# Sheet1.net
KiCad netlist of a schematic drawn in Altium Designer
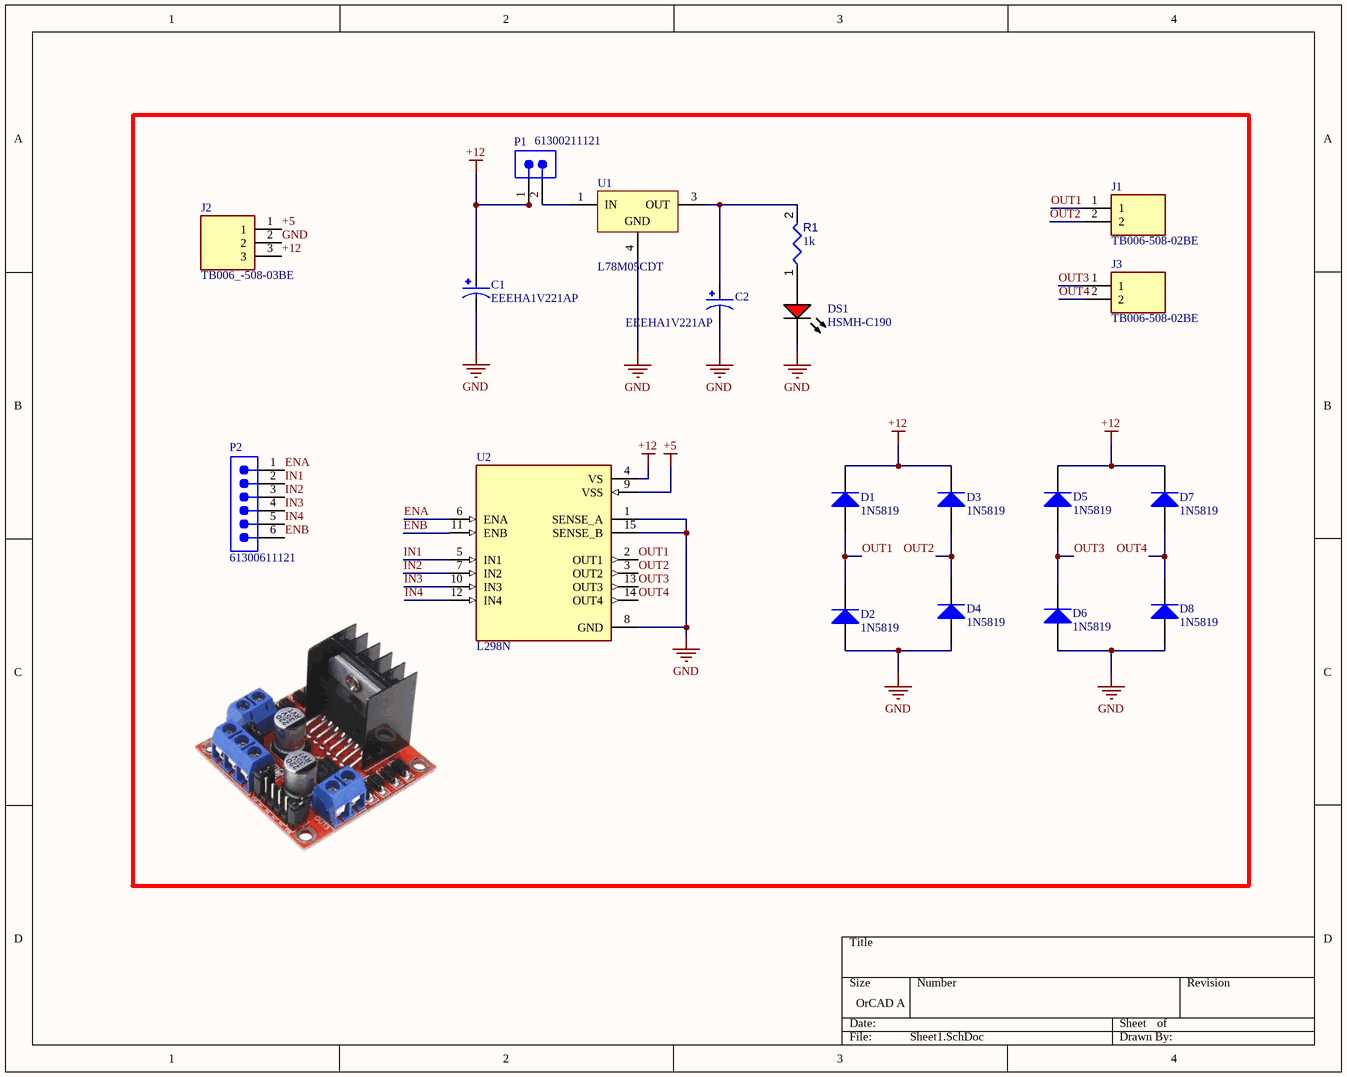
[diagram p0: Sheet1.SchDoc]

(export (version "E")
  (design (tool "Eeschema 10.0.6"))
  (components
    (comp (ref "C1")
      (value "EEEHA1V221AP")
      (footprint "CAP_EEEHA1V221AP")
      (description "220ÂµF 35V Aluminum Electrolytic Capacitors Radial, Can - SMD 1000 Hrs @ 105Â°C")
      (fields (field (name "MP") "EEE-HA1V221AP") (field (name "MF") "Panasonic"))
      (libsource (lib "cap") (part "EEEHA1V221AP"))
    )
    (comp (ref "C2")
      (value "EEEHA1V221AP")
      (footprint "CAP_EEEHA1V221AP")
      (description "220ÂµF 35V Aluminum Electrolytic Capacitors Radial, Can - SMD 1000 Hrs @ 105Â°C")
      (fields (field (name "MP") "EEE-HA1V221AP") (field (name "MF") "Panasonic"))
      (libsource (lib "cap") (part "EEEHA1V221AP"))
    )
    (comp (ref "D1")
      (value "1N5819")
      (footprint "ONSC-AXIAL_LEAD-2-59-10_P")
      (description "Low Drop Power Schottky Rectifier, 40 V, 1 A, 2-Pin DO-41, RoHS")
      (fields (field (name "MANUFACTURER") "ON Semiconductor"))
      (libsource (lib "Med khalil khlifi") (part "D-AK-2"))
    )
    (comp (ref "D2")
      (value "1N5819")
      (footprint "ONSC-AXIAL_LEAD-2-59-10_P")
      (description "Low Drop Power Schottky Rectifier, 40 V, 1 A, 2-Pin DO-41, RoHS")
      (fields (field (name "MANUFACTURER") "ON Semiconductor"))
      (libsource (lib "Med khalil khlifi") (part "D-AK-2"))
    )
    (comp (ref "D3")
      (value "1N5819")
      (footprint "ONSC-AXIAL_LEAD-2-59-10_P")
      (description "Low Drop Power Schottky Rectifier, 40 V, 1 A, 2-Pin DO-41, RoHS")
      (fields (field (name "MANUFACTURER") "ON Semiconductor"))
      (libsource (lib "Med khalil khlifi") (part "D-AK-2"))
    )
    (comp (ref "D4")
      (value "1N5819")
      (footprint "ONSC-AXIAL_LEAD-2-59-10_P")
      (description "Low Drop Power Schottky Rectifier, 40 V, 1 A, 2-Pin DO-41, RoHS")
      (fields (field (name "MANUFACTURER") "ON Semiconductor"))
      (libsource (lib "Med khalil khlifi") (part "D-AK-2"))
    )
    (comp (ref "D5")
      (value "1N5819")
      (footprint "ONSC-AXIAL_LEAD-2-59-10_P")
      (description "Low Drop Power Schottky Rectifier, 40 V, 1 A, 2-Pin DO-41, RoHS")
      (fields (field (name "MANUFACTURER") "ON Semiconductor"))
      (libsource (lib "Med khalil khlifi") (part "D-AK-2"))
    )
    (comp (ref "D6")
      (value "1N5819")
      (footprint "ONSC-AXIAL_LEAD-2-59-10_P")
      (description "Low Drop Power Schottky Rectifier, 40 V, 1 A, 2-Pin DO-41, RoHS")
      (fields (field (name "MANUFACTURER") "ON Semiconductor"))
      (libsource (lib "Med khalil khlifi") (part "D-AK-2"))
    )
    (comp (ref "D7")
      (value "1N5819")
      (footprint "ONSC-AXIAL_LEAD-2-59-10_P")
      (description "Low Drop Power Schottky Rectifier, 40 V, 1 A, 2-Pin DO-41, RoHS")
      (fields (field (name "MANUFACTURER") "ON Semiconductor"))
      (libsource (lib "Med khalil khlifi") (part "D-AK-2"))
    )
    (comp (ref "D8")
      (value "1N5819")
      (footprint "ONSC-AXIAL_LEAD-2-59-10_P")
      (description "Low Drop Power Schottky Rectifier, 40 V, 1 A, 2-Pin DO-41, RoHS")
      (fields (field (name "MANUFACTURER") "ON Semiconductor"))
      (libsource (lib "Med khalil khlifi") (part "D-AK-2"))
    )
    (comp (ref "DS1")
      (value "HSMH-C190")
      (footprint "AVAG-HSMX-C190_V")
      (description "LED Uni-Color Red, 65 mW, 20 mA, -40 to 85 degC, 2-Pin SMD, RoHS, Tape and Reel")
      (fields (field (name "POWER") "78mW") (field (name "MANUFACTURER") "Avago"))
      (libsource (lib "Med khalil khlifi") (part "LED-RED-AK-2"))
    )
    (comp (ref "J1")
      (value "TB006-508-02BE")
      (footprint "CUI_TB006-508-02BE")
      (description "2~24 Poles, Screw Type, Horizontal, 5.08 Pitch, 26~14 (AWG), Terminal Block Connector")
      (fields (field (name "MF") "Same Sky"))
      (libsource (lib "TB006-508-02BE") (part "TB006-508-02BE"))
    )
    (comp (ref "J2")
      (value "TB006_-508-03BE")
      (footprint "CUI_TB006 -508-03BE")
      (description "2~24 Poles, Screw Type, Horizontal, 5.08 Pitch, 26~14 (AWG), Terminal Block Connector")
      (fields (field (name "MF") "CUI Devices") (field (name "MP") "TB006 -508-03BE"))
      (libsource (lib "TB006_-508-03BE") (part "TB006_-508-03BE"))
    )
    (comp (ref "J3")
      (value "TB006-508-02BE")
      (footprint "CUI_TB006-508-02BE")
      (description "2~24 Poles, Screw Type, Horizontal, 5.08 Pitch, 26~14 (AWG), Terminal Block Connector")
      (fields (field (name "MF") "Same Sky"))
      (libsource (lib "TB006-508-02BE") (part "TB006-508-02BE"))
    )
    (comp (ref "P1")
      (value "61300211121")
      (footprint "61300211121")
      (libsource (lib "pin header 2") (part "CMP-1712-00002-6"))
    )
    (comp (ref "P2")
      (value "61300611121")
      (footprint "61300611121")
      (libsource (lib "header 6") (part "CMP-1502-01070-3"))
    )
    (comp (ref "R1")
      (value "1k")
      (footprint "RESC0402(1005)_L")
      (description "Chip Resistor, 1 kOhms, +/-5 %, 63 mW, -55 to 155 degC, 0402")
      (fields (field (name "TOLERANCE") "5%") (field (name "POWER") "63mW"))
      (libsource (lib "Med khalil khlifi") (part "RES-2"))
    )
    (comp (ref "U1")
      (value "L78M05CDT")
      (footprint "STM-TO252-3_A_V")
      (description "Precision Regulator, 0.5 A, 5 V Output, 0 to 150 degC, 3-Pin DPAK (TO252), RoHS, Tube")
      (fields (field (name "MANUFACTURER") "STMicroelectronics"))
      (libsource (lib "78M05") (part "CMP-2000-06530-1"))
    )
    (comp (ref "U2")
      (value "L298N")
      (footprint "TO127P2020X500X2100-15")
      (description "Dual Full Bridge Motor Driver 15-Pin(15+Tab) MULTIWATT V Tube")
      (libsource (lib "L298N") (part "L298N"))
    )
  )
  (nets
    (net (code "1") (name "+5") (class "Default")
      (node (ref "J2") (pin "1") (pinfunction "1_1") (pintype "passive"))
      (node (ref "U2") (pin "9") (pinfunction "VSS_9") (pintype "input"))
    )
    (net (code "2") (name "+12") (class "Default")
      (node (ref "C1") (pin "1") (pinfunction "1_1") (pintype "passive"))
      (node (ref "D1") (pin "2") (pinfunction "K_2") (pintype "passive"))
      (node (ref "D3") (pin "2") (pinfunction "K_2") (pintype "passive"))
      (node (ref "D5") (pin "2") (pinfunction "K_2") (pintype "passive"))
      (node (ref "D7") (pin "2") (pinfunction "K_2") (pintype "passive"))
      (node (ref "J2") (pin "3") (pinfunction "3_3") (pintype "passive"))
      (node (ref "P1") (pin "1") (pinfunction "1_1") (pintype "passive"))
      (node (ref "U2") (pin "4") (pinfunction "VS_4") (pintype "power_in"))
    )
    (net (code "3") (name "/ENA") (class "Default")
      (node (ref "P2") (pin "1") (pinfunction "1_1") (pintype "passive"))
      (node (ref "U2") (pin "6") (pinfunction "ENA_6") (pintype "input"))
    )
    (net (code "4") (name "/ENB") (class "Default")
      (node (ref "P2") (pin "6") (pinfunction "6_6") (pintype "passive"))
      (node (ref "U2") (pin "11") (pinfunction "ENB_11") (pintype "input"))
    )
    (net (code "5") (name "/IN1") (class "Default")
      (node (ref "P2") (pin "2") (pinfunction "2_2") (pintype "passive"))
      (node (ref "U2") (pin "5") (pinfunction "IN1_5") (pintype "input"))
    )
    (net (code "6") (name "/IN2") (class "Default")
      (node (ref "P2") (pin "3") (pinfunction "3_3") (pintype "passive"))
      (node (ref "U2") (pin "7") (pinfunction "IN2_7") (pintype "input"))
    )
    (net (code "7") (name "/IN3") (class "Default")
      (node (ref "P2") (pin "4") (pinfunction "4_4") (pintype "passive"))
      (node (ref "U2") (pin "10") (pinfunction "IN3_10") (pintype "input"))
    )
    (net (code "8") (name "/IN4") (class "Default")
      (node (ref "P2") (pin "5") (pinfunction "5_5") (pintype "passive"))
      (node (ref "U2") (pin "12") (pinfunction "IN4_12") (pintype "input"))
    )
    (net (code "9") (name "/OUT1") (class "Default")
      (node (ref "D1") (pin "1") (pinfunction "A_1") (pintype "passive"))
      (node (ref "D2") (pin "2") (pinfunction "K_2") (pintype "passive"))
      (node (ref "J1") (pin "1") (pinfunction "1_1") (pintype "passive"))
      (node (ref "U2") (pin "2") (pinfunction "OUT1_2") (pintype "output"))
    )
    (net (code "10") (name "/OUT2") (class "Default")
      (node (ref "D3") (pin "1") (pinfunction "A_1") (pintype "passive"))
      (node (ref "D4") (pin "2") (pinfunction "K_2") (pintype "passive"))
      (node (ref "J1") (pin "2") (pinfunction "2_2") (pintype "passive"))
      (node (ref "U2") (pin "3") (pinfunction "OUT2_3") (pintype "output"))
    )
    (net (code "11") (name "/OUT3") (class "Default")
      (node (ref "D5") (pin "1") (pinfunction "A_1") (pintype "passive"))
      (node (ref "D6") (pin "2") (pinfunction "K_2") (pintype "passive"))
      (node (ref "J3") (pin "1") (pinfunction "1_1") (pintype "passive"))
      (node (ref "U2") (pin "13") (pinfunction "OUT3_13") (pintype "output"))
    )
    (net (code "12") (name "/OUT4") (class "Default")
      (node (ref "D7") (pin "1") (pinfunction "A_1") (pintype "passive"))
      (node (ref "D8") (pin "2") (pinfunction "K_2") (pintype "passive"))
      (node (ref "J3") (pin "2") (pinfunction "2_2") (pintype "passive"))
      (node (ref "U2") (pin "14") (pinfunction "OUT4_14") (pintype "output"))
    )
    (net (code "13") (name "GND") (class "Default")
      (node (ref "C1") (pin "2") (pinfunction "2_2") (pintype "passive"))
      (node (ref "C2") (pin "2") (pinfunction "2_2") (pintype "passive"))
      (node (ref "D2") (pin "1") (pinfunction "A_1") (pintype "passive"))
      (node (ref "D4") (pin "1") (pinfunction "A_1") (pintype "passive"))
      (node (ref "D6") (pin "1") (pinfunction "A_1") (pintype "passive"))
      (node (ref "D8") (pin "1") (pinfunction "A_1") (pintype "passive"))
      (node (ref "DS1") (pin "2") (pinfunction "K_2") (pintype "passive"))
      (node (ref "J2") (pin "2") (pinfunction "2_2") (pintype "passive"))
      (node (ref "U1") (pin "4") (pinfunction "GND_4") (pintype "power_in"))
      (node (ref "U2") (pin "1") (pinfunction "SENSE_A_1") (pintype "passive"))
      (node (ref "U2") (pin "15") (pinfunction "SENSE_B_15") (pintype "passive"))
      (node (ref "U2") (pin "8") (pinfunction "GND_8") (pintype "power_in"))
    )
    (net (code "14") (name "Net-(DS1-A)") (class "Default")
      (node (ref "DS1") (pin "1") (pinfunction "A_1") (pintype "passive"))
      (node (ref "R1") (pin "1") (pinfunction "1_1") (pintype "passive"))
    )
    (net (code "15") (name "Net-(U1-IN)") (class "Default")
      (node (ref "P1") (pin "2") (pinfunction "2_2") (pintype "passive"))
      (node (ref "U1") (pin "1") (pinfunction "IN_1") (pintype "power_in"))
    )
    (net (code "16") (name "Net-(U1-OUT)") (class "Default")
      (node (ref "C2") (pin "1") (pinfunction "1_1") (pintype "passive"))
      (node (ref "R1") (pin "2") (pinfunction "2_2") (pintype "passive"))
      (node (ref "U1") (pin "3") (pinfunction "OUT_3") (pintype "power_in"))
    )
  )
)
